# SCH_NFC-Business-card_2024-05-23.net
KiCad netlist of a schematic drawn in EasyEDA
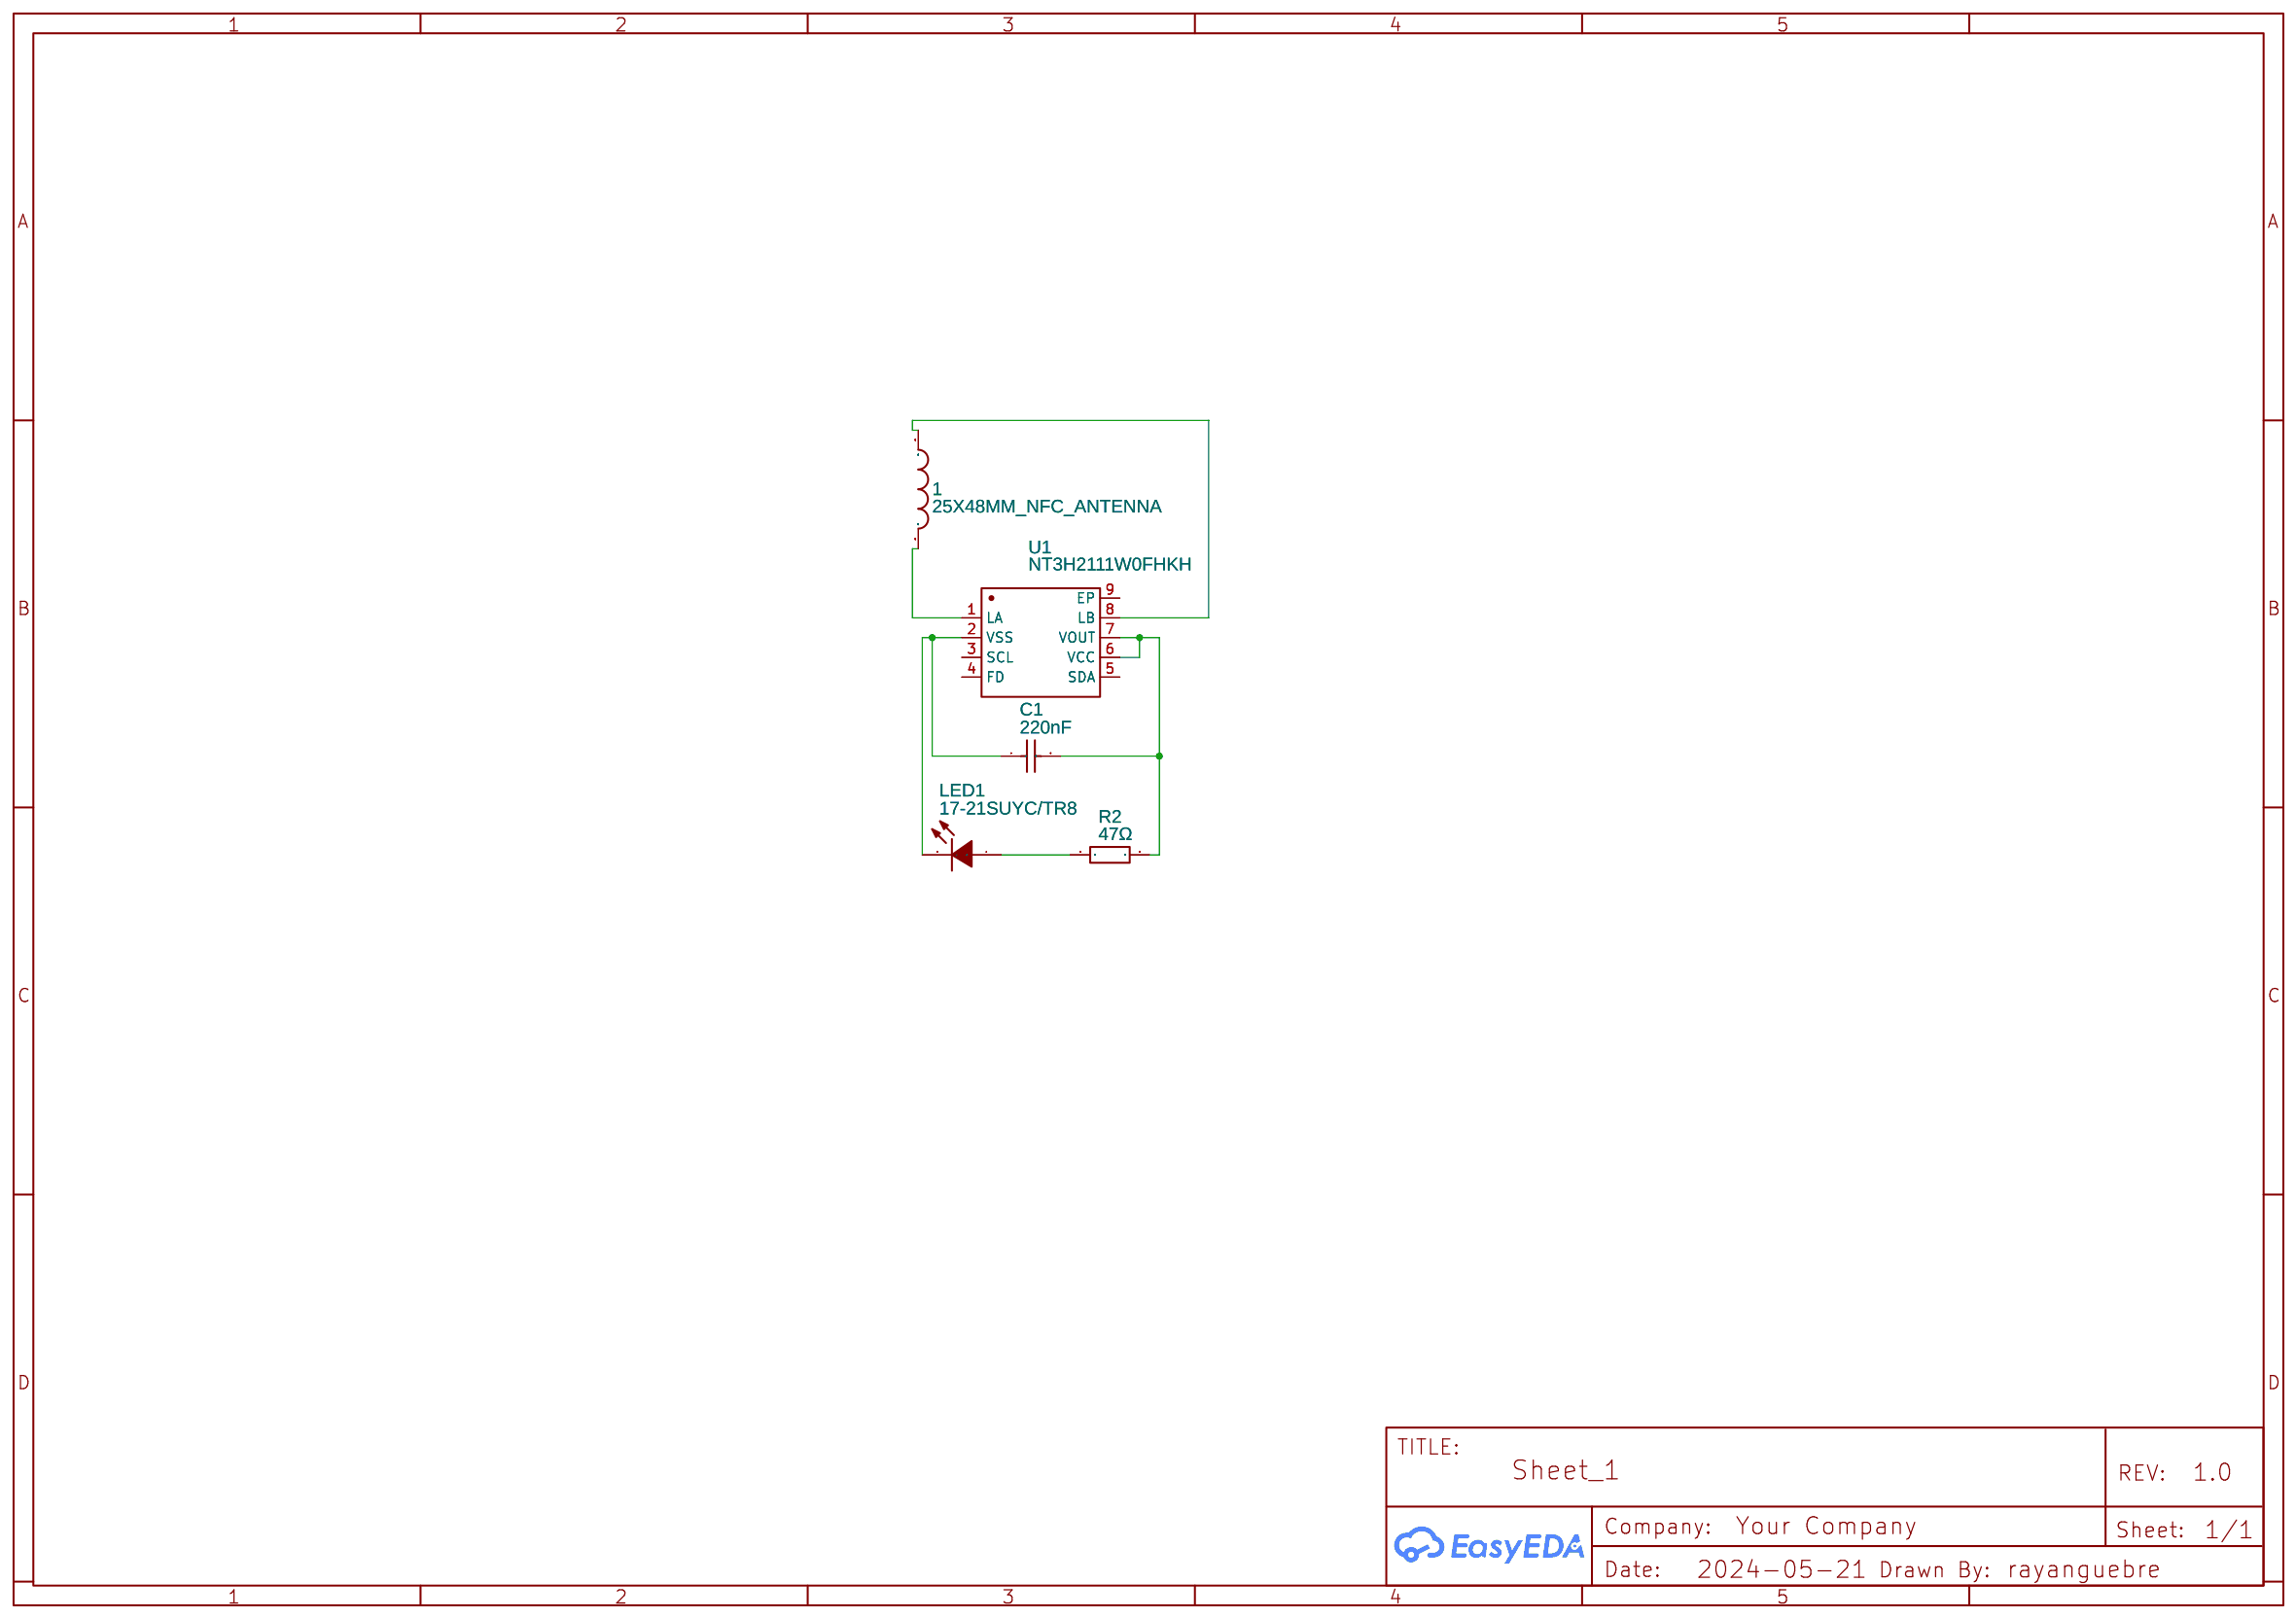
[diagram p0: schematic sheet]

(export (version "E")
  (design (tool "Eeschema 10.0.6"))
  (components
    (comp (ref "1") (value "25X48MM_NFC_ANTENNA") (libsource (lib "") (part "25X48MM_NFC_ANTENNA")))
    (comp (ref "C1")
      (value "220nF")
      (fields
        (field (name "Manufacturer Part") "CL21B224KBFNNNE")
        (field (name "Manufacturer") "SAMSUNG(三星)")
      )
      (libsource (lib "") (part "CL21B224KBFNNNE"))
    )
    (comp (ref "LED1")
      (value "17-21SUYC/TR8")
      (fields (field (name "Manufacturer Part") "KT-0805黄灯") (field (name "Manufacturer") "KENTO"))
      (libsource (lib "") (part "17-21SUYC/TR8"))
    )
    (comp (ref "R2")
      (value "47Ω")
      (fields
        (field (name "Manufacturer Part") "0603WAF470JT5E")
        (field (name "Manufacturer") "UNI-ROYAL(厚声)")
      )
      (libsource (lib "") (part "0603WAF470JT5E"))
    )
    (comp (ref "U1")
      (value "NT3H2111W0FHKH")
      (fields (field (name "Manufacturer") "NXP(恩智浦)"))
      (libsource (lib "") (part "NT3H2111W0FHKH"))
    )
  )
  (nets
    (net (code "1") (name "Net-(LED1-+)") (class "Default")
      (node (ref "LED1") (pin "1") (pinfunction "+_1") (pintype "unspecified"))
      (node (ref "R2") (pin "1") (pinfunction "1_1") (pintype "input"))
    )
    (net (code "2") (name "Net-(LED1--)") (class "Default")
      (node (ref "C1") (pin "1") (pinfunction "1_1") (pintype "input"))
      (node (ref "LED1") (pin "2") (pinfunction "-_2") (pintype "unspecified"))
      (node (ref "U1") (pin "2") (pinfunction "VSS_2") (pintype "unspecified"))
    )
    (net (code "3") (name "Net-(U1-LA)") (class "Default")
      (node (ref "1") (pin "P$2") (pinfunction "P$2_P$2") (pintype "bidirectional"))
      (node (ref "U1") (pin "1") (pinfunction "LA_1") (pintype "unspecified"))
    )
    (net (code "4") (name "Net-(U1-LB)") (class "Default")
      (node (ref "1") (pin "P$1") (pinfunction "P$1_P$1") (pintype "bidirectional"))
      (node (ref "U1") (pin "8") (pinfunction "LB_8") (pintype "unspecified"))
    )
    (net (code "5") (name "Net-(U1-VCC)") (class "Default")
      (node (ref "C1") (pin "2") (pinfunction "2_2") (pintype "input"))
      (node (ref "R2") (pin "2") (pinfunction "2_2") (pintype "input"))
      (node (ref "U1") (pin "6") (pinfunction "VCC_6") (pintype "unspecified"))
      (node (ref "U1") (pin "7") (pinfunction "VOUT_7") (pintype "unspecified"))
    )
    (net (code "6") (name "unconnected-(U1-EP-Pad9)") (class "Default")
      (node (ref "U1") (pin "9") (pinfunction "EP_9") (pintype "unspecified"))
    )
    (net (code "7") (name "unconnected-(U1-FD-Pad4)") (class "Default")
      (node (ref "U1") (pin "4") (pinfunction "FD_4") (pintype "unspecified"))
    )
    (net (code "8") (name "unconnected-(U1-SCL-Pad3)") (class "Default")
      (node (ref "U1") (pin "3") (pinfunction "SCL_3") (pintype "unspecified"))
    )
    (net (code "9") (name "unconnected-(U1-SDA-Pad5)") (class "Default")
      (node (ref "U1") (pin "5") (pinfunction "SDA_5") (pintype "unspecified"))
    )
  )
)
